# Mainboard_Encoder_Interface.net
KiCad netlist of a schematic drawn in Altium Designer
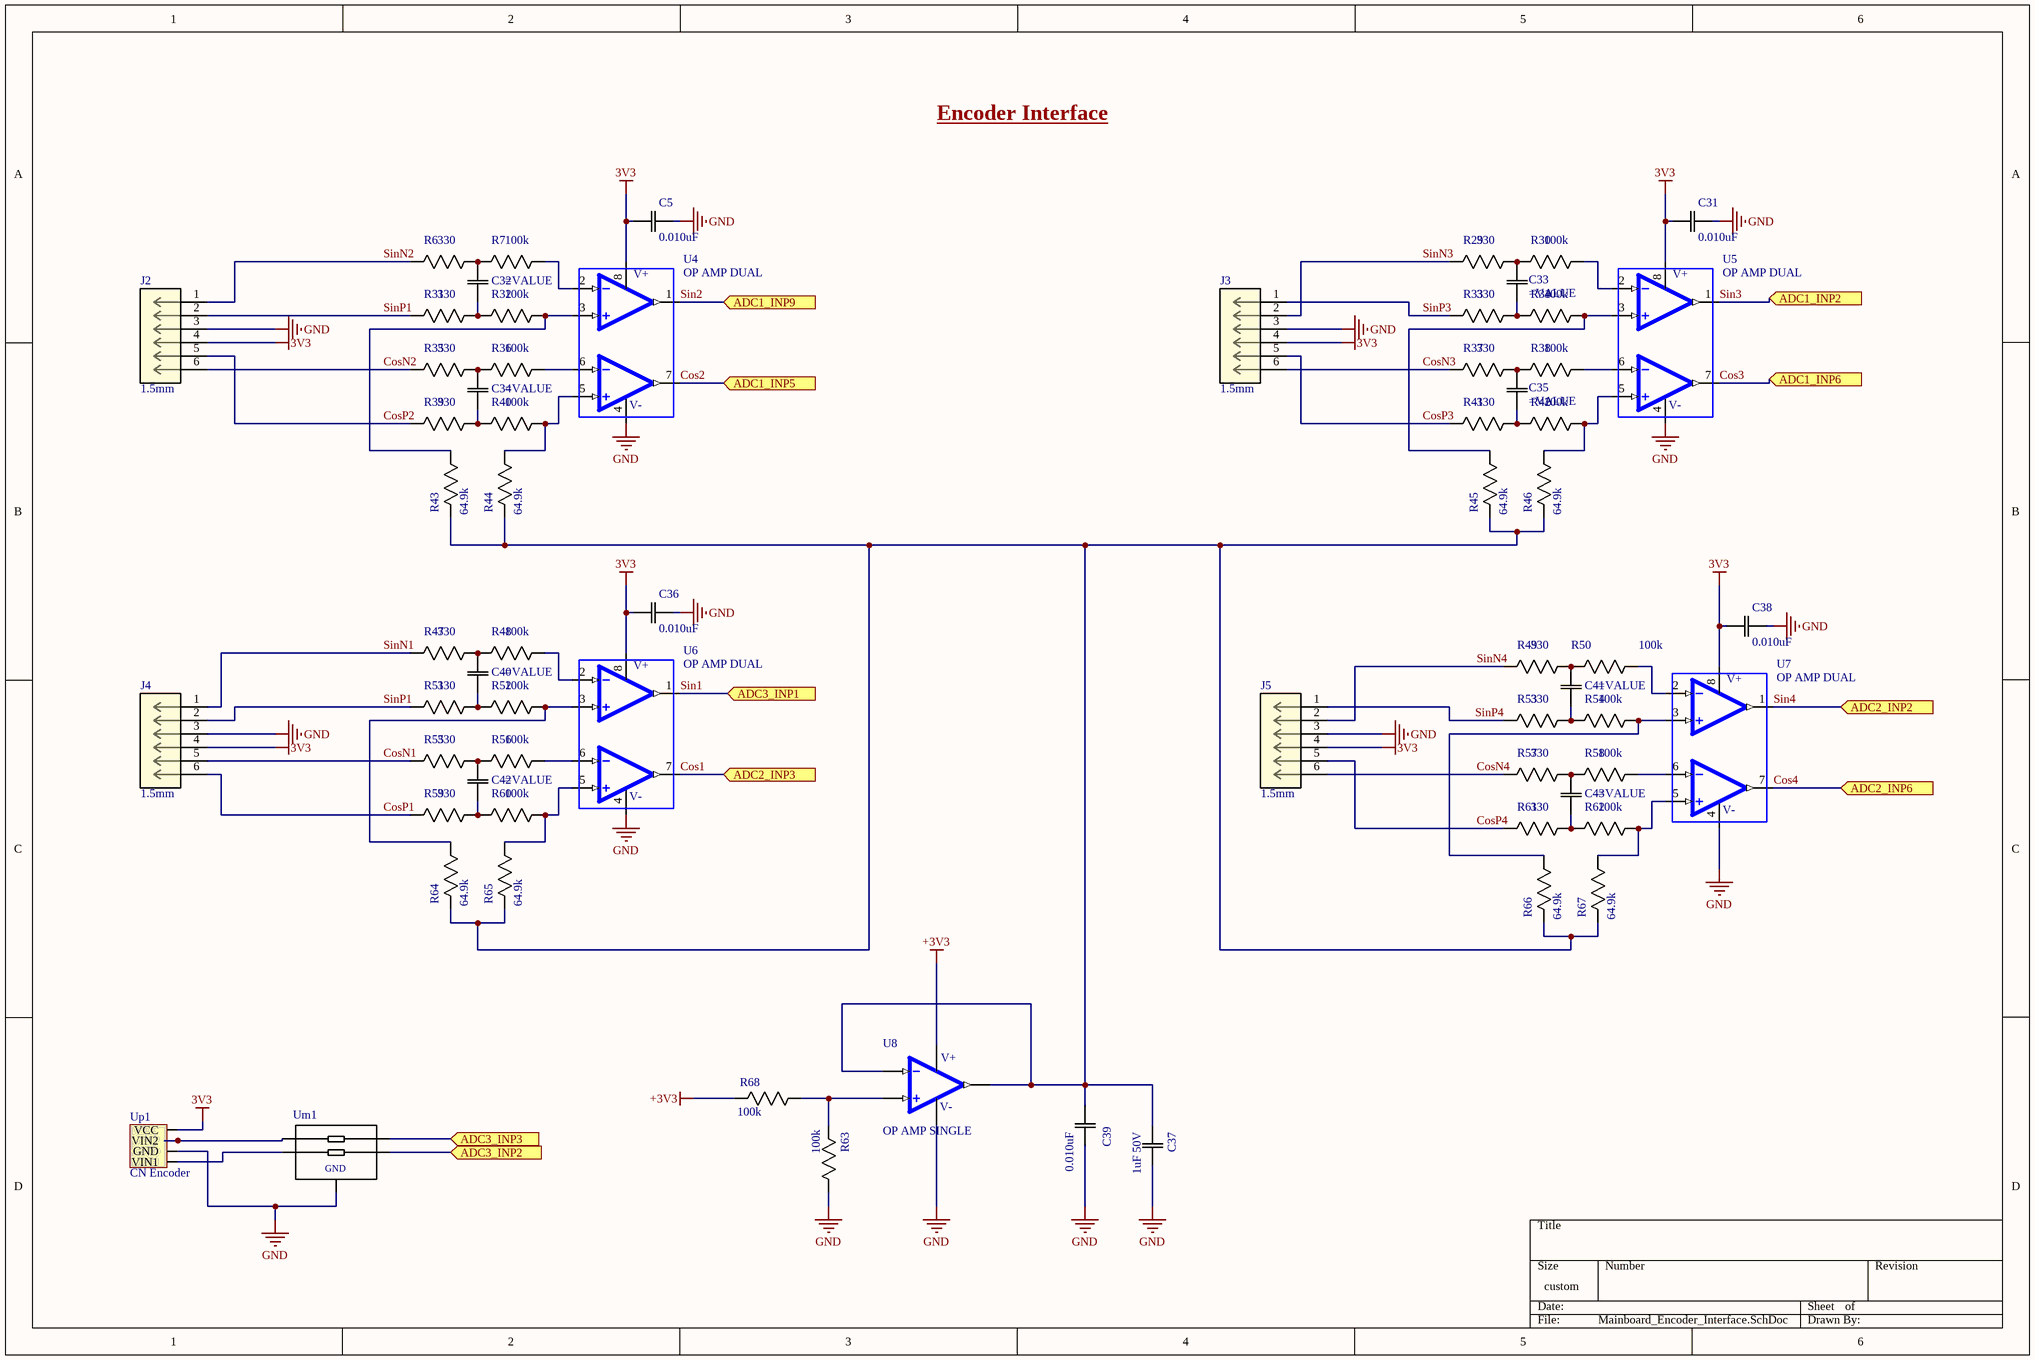
[diagram p0: Mainboard_Encoder_Interface.SchDoc]

(export (version "E")
  (design (tool "Eeschema 10.0.6"))
  (components
    (comp (ref "C5")
      (value "0.010uF")
      (footprint "0603")
      (description "CAP CER 0.010UF 50V X7R 0603/0805")
      (fields (field (name "TOLERANCE") "10%"))
      (libsource (lib "AltiumLibraries") (part "CAP 0.010uF 50V"))
    )
    (comp (ref "C31")
      (value "0.010uF")
      (footprint "0603")
      (description "CAP CER 0.010UF 50V X7R 0603/0805")
      (fields (field (name "TOLERANCE") "10%"))
      (libsource (lib "AltiumLibraries") (part "CAP 0.010uF 50V"))
    )
    (comp (ref "C32") (value "~") (libsource (lib "AltiumLibraries") (part "CAPACITOR_SCH")))
    (comp (ref "C33") (value "~") (libsource (lib "AltiumLibraries") (part "CAPACITOR_SCH")))
    (comp (ref "C34") (value "~") (libsource (lib "AltiumLibraries") (part "CAPACITOR_SCH")))
    (comp (ref "C35") (value "~") (libsource (lib "AltiumLibraries") (part "CAPACITOR_SCH")))
    (comp (ref "C36")
      (value "0.010uF")
      (footprint "0603")
      (description "CAP CER 0.010UF 50V X7R 0603/0805")
      (fields (field (name "TOLERANCE") "10%"))
      (libsource (lib "AltiumLibraries") (part "CAP 0.010uF 50V"))
    )
    (comp (ref "C37")
      (value "1uF 50V")
      (footprint "0805")
      (description "CAP CER 1UF 50V X7R 0805")
      (fields (field (name "TOLERANCE") "10%"))
      (libsource (lib "AltiumLibraries") (part "CAP 1uF 50V"))
    )
    (comp (ref "C38")
      (value "0.010uF")
      (footprint "0603")
      (description "CAP CER 0.010UF 50V X7R 0603/0805")
      (fields (field (name "TOLERANCE") "10%"))
      (libsource (lib "AltiumLibraries") (part "CAP 0.010uF 50V"))
    )
    (comp (ref "C39")
      (value "0.010uF")
      (footprint "0603")
      (description "CAP CER 0.010UF 50V X7R 0603/0805")
      (fields (field (name "TOLERANCE") "10%"))
      (libsource (lib "AltiumLibraries") (part "CAP 0.010uF 50V"))
    )
    (comp (ref "C40") (value "~") (libsource (lib "AltiumLibraries") (part "CAPACITOR_SCH")))
    (comp (ref "C41") (value "~") (libsource (lib "AltiumLibraries") (part "CAPACITOR_SCH")))
    (comp (ref "C42") (value "~") (libsource (lib "AltiumLibraries") (part "CAPACITOR_SCH")))
    (comp (ref "C43") (value "~") (libsource (lib "AltiumLibraries") (part "CAPACITOR_SCH")))
    (comp (ref "J2")
      (value "1.5mm")
      (footprint "6POS JST")
      (description "Conn Shrouded Header HDR 6 POS 1.5mm Solder RA Thru-Hole Box")
      (fields (field (name "MANUFACTURER") "JST") (field (name "MANUFACTURER PART NUMBER") "S6B-ZR(LF)(SN)"))
      (libsource (lib "AltiumLibraries") (part "CN 6POS JST RA"))
    )
    (comp (ref "J3")
      (value "1.5mm")
      (footprint "6POS JST")
      (description "Conn Shrouded Header HDR 6 POS 1.5mm Solder RA Thru-Hole Box")
      (fields (field (name "MANUFACTURER") "JST") (field (name "MANUFACTURER PART NUMBER") "S6B-ZR(LF)(SN)"))
      (libsource (lib "AltiumLibraries") (part "CN 6POS JST RA"))
    )
    (comp (ref "J4")
      (value "1.5mm")
      (footprint "6POS JST")
      (description "Conn Shrouded Header HDR 6 POS 1.5mm Solder RA Thru-Hole Box")
      (fields (field (name "MANUFACTURER") "JST") (field (name "MANUFACTURER PART NUMBER") "S6B-ZR(LF)(SN)"))
      (libsource (lib "AltiumLibraries") (part "CN 6POS JST RA"))
    )
    (comp (ref "J5")
      (value "1.5mm")
      (footprint "6POS JST")
      (description "Conn Shrouded Header HDR 6 POS 1.5mm Solder RA Thru-Hole Box")
      (fields (field (name "MANUFACTURER") "JST") (field (name "MANUFACTURER PART NUMBER") "S6B-ZR(LF)(SN)"))
      (libsource (lib "AltiumLibraries") (part "CN 6POS JST RA"))
    )
    (comp (ref "R6")
      (value "330")
      (footprint "0805")
      (description "RES SMD 330 OHM 1% 1/8W 0805")
      (fields (field (name "TOLERANCE") "1%"))
      (libsource (lib "") (part "RES 330.0 1/8W - 1%_1"))
    )
    (comp (ref "R7")
      (value "100k")
      (footprint "0805")
      (description "RES SMD 100K OHM 1% 1/8W 0805")
      (fields (field (name "TOLERANCE") "1%"))
      (libsource (lib "") (part "RES 100k 1/8W - 1%_1"))
    )
    (comp (ref "R29")
      (value "330")
      (footprint "0805")
      (description "RES SMD 330 OHM 1% 1/8W 0805")
      (fields (field (name "TOLERANCE") "1%"))
      (libsource (lib "") (part "RES 330.0 1/8W - 1%_1"))
    )
    (comp (ref "R30")
      (value "100k")
      (footprint "0805")
      (description "RES SMD 100K OHM 1% 1/8W 0805")
      (fields (field (name "TOLERANCE") "1%"))
      (libsource (lib "") (part "RES 100k 1/8W - 1%_1"))
    )
    (comp (ref "R31")
      (value "330")
      (footprint "0805")
      (description "RES SMD 330 OHM 1% 1/8W 0805")
      (fields (field (name "TOLERANCE") "1%"))
      (libsource (lib "AltiumLibraries") (part "RES 330.0 1/8W - 1%"))
    )
    (comp (ref "R32")
      (value "100k")
      (footprint "0805")
      (description "RES SMD 100K OHM 1% 1/8W 0805")
      (fields (field (name "TOLERANCE") "1%"))
      (libsource (lib "AltiumLibraries") (part "RES 100k 1/8W - 1%"))
    )
    (comp (ref "R33")
      (value "330")
      (footprint "0805")
      (description "RES SMD 330 OHM 1% 1/8W 0805")
      (fields (field (name "TOLERANCE") "1%"))
      (libsource (lib "AltiumLibraries") (part "RES 330.0 1/8W - 1%"))
    )
    (comp (ref "R34")
      (value "100k")
      (footprint "0805")
      (description "RES SMD 100K OHM 1% 1/8W 0805")
      (fields (field (name "TOLERANCE") "1%"))
      (libsource (lib "AltiumLibraries") (part "RES 100k 1/8W - 1%"))
    )
    (comp (ref "R35")
      (value "330")
      (footprint "0805")
      (description "RES SMD 330 OHM 1% 1/8W 0805")
      (fields (field (name "TOLERANCE") "1%"))
      (libsource (lib "") (part "RES 330.0 1/8W - 1%_1"))
    )
    (comp (ref "R36")
      (value "100k")
      (footprint "0805")
      (description "RES SMD 100K OHM 1% 1/8W 0805")
      (fields (field (name "TOLERANCE") "1%"))
      (libsource (lib "") (part "RES 100k 1/8W - 1%_1"))
    )
    (comp (ref "R37")
      (value "330")
      (footprint "0805")
      (description "RES SMD 330 OHM 1% 1/8W 0805")
      (fields (field (name "TOLERANCE") "1%"))
      (libsource (lib "") (part "RES 330.0 1/8W - 1%_1"))
    )
    (comp (ref "R38")
      (value "100k")
      (footprint "0805")
      (description "RES SMD 100K OHM 1% 1/8W 0805")
      (fields (field (name "TOLERANCE") "1%"))
      (libsource (lib "") (part "RES 100k 1/8W - 1%_1"))
    )
    (comp (ref "R39")
      (value "330")
      (footprint "0805")
      (description "RES SMD 330 OHM 1% 1/8W 0805")
      (fields (field (name "TOLERANCE") "1%"))
      (libsource (lib "AltiumLibraries") (part "RES 330.0 1/8W - 1%"))
    )
    (comp (ref "R40")
      (value "100k")
      (footprint "0805")
      (description "RES SMD 100K OHM 1% 1/8W 0805")
      (fields (field (name "TOLERANCE") "1%"))
      (libsource (lib "AltiumLibraries") (part "RES 100k 1/8W - 1%"))
    )
    (comp (ref "R41")
      (value "330")
      (footprint "0805")
      (description "RES SMD 330 OHM 1% 1/8W 0805")
      (fields (field (name "TOLERANCE") "1%"))
      (libsource (lib "AltiumLibraries") (part "RES 330.0 1/8W - 1%"))
    )
    (comp (ref "R42")
      (value "100k")
      (footprint "0805")
      (description "RES SMD 100K OHM 1% 1/8W 0805")
      (fields (field (name "TOLERANCE") "1%"))
      (libsource (lib "AltiumLibraries") (part "RES 100k 1/8W - 1%"))
    )
    (comp (ref "R43")
      (value "64.9k")
      (footprint "0805")
      (description "RES SMD 64.9K OHM 1% 1/8W 0805")
      (fields (field (name "TOLERANCE") "1%"))
      (libsource (lib "AltiumLibraries") (part "RES 64.9k 1/8W"))
    )
    (comp (ref "R44")
      (value "64.9k")
      (footprint "0805")
      (description "RES SMD 64.9K OHM 1% 1/8W 0805")
      (fields (field (name "TOLERANCE") "1%"))
      (libsource (lib "AltiumLibraries") (part "RES 64.9k 1/8W"))
    )
    (comp (ref "R45")
      (value "64.9k")
      (footprint "0805")
      (description "RES SMD 64.9K OHM 1% 1/8W 0805")
      (fields (field (name "TOLERANCE") "1%"))
      (libsource (lib "AltiumLibraries") (part "RES 64.9k 1/8W"))
    )
    (comp (ref "R46")
      (value "64.9k")
      (footprint "0805")
      (description "RES SMD 64.9K OHM 1% 1/8W 0805")
      (fields (field (name "TOLERANCE") "1%"))
      (libsource (lib "AltiumLibraries") (part "RES 64.9k 1/8W"))
    )
    (comp (ref "R47")
      (value "330")
      (footprint "0805")
      (description "RES SMD 330 OHM 1% 1/8W 0805")
      (fields (field (name "TOLERANCE") "1%"))
      (libsource (lib "") (part "RES 330.0 1/8W - 1%_1"))
    )
    (comp (ref "R48")
      (value "100k")
      (footprint "0805")
      (description "RES SMD 100K OHM 1% 1/8W 0805")
      (fields (field (name "TOLERANCE") "1%"))
      (libsource (lib "") (part "RES 100k 1/8W - 1%_1"))
    )
    (comp (ref "R49")
      (value "330")
      (footprint "0805")
      (description "RES SMD 330 OHM 1% 1/8W 0805")
      (fields (field (name "TOLERANCE") "1%"))
      (libsource (lib "") (part "RES 330.0 1/8W - 1%_1"))
    )
    (comp (ref "R50")
      (value "100k")
      (footprint "0805")
      (description "RES SMD 100K OHM 1% 1/8W 0805")
      (fields (field (name "TOLERANCE") "1%"))
      (libsource (lib "") (part "RES 100k 1/8W - 1%_1"))
    )
    (comp (ref "R51")
      (value "330")
      (footprint "0805")
      (description "RES SMD 330 OHM 1% 1/8W 0805")
      (fields (field (name "TOLERANCE") "1%"))
      (libsource (lib "AltiumLibraries") (part "RES 330.0 1/8W - 1%"))
    )
    (comp (ref "R52")
      (value "100k")
      (footprint "0805")
      (description "RES SMD 100K OHM 1% 1/8W 0805")
      (fields (field (name "TOLERANCE") "1%"))
      (libsource (lib "AltiumLibraries") (part "RES 100k 1/8W - 1%"))
    )
    (comp (ref "R53")
      (value "330")
      (footprint "0805")
      (description "RES SMD 330 OHM 1% 1/8W 0805")
      (fields (field (name "TOLERANCE") "1%"))
      (libsource (lib "AltiumLibraries") (part "RES 330.0 1/8W - 1%"))
    )
    (comp (ref "R54")
      (value "100k")
      (footprint "0805")
      (description "RES SMD 100K OHM 1% 1/8W 0805")
      (fields (field (name "TOLERANCE") "1%"))
      (libsource (lib "AltiumLibraries") (part "RES 100k 1/8W - 1%"))
    )
    (comp (ref "R55")
      (value "330")
      (footprint "0805")
      (description "RES SMD 330 OHM 1% 1/8W 0805")
      (fields (field (name "TOLERANCE") "1%"))
      (libsource (lib "") (part "RES 330.0 1/8W - 1%_1"))
    )
    (comp (ref "R56")
      (value "100k")
      (footprint "0805")
      (description "RES SMD 100K OHM 1% 1/8W 0805")
      (fields (field (name "TOLERANCE") "1%"))
      (libsource (lib "") (part "RES 100k 1/8W - 1%_1"))
    )
    (comp (ref "R57")
      (value "330")
      (footprint "0805")
      (description "RES SMD 330 OHM 1% 1/8W 0805")
      (fields (field (name "TOLERANCE") "1%"))
      (libsource (lib "") (part "RES 330.0 1/8W - 1%_1"))
    )
    (comp (ref "R58")
      (value "100k")
      (footprint "0805")
      (description "RES SMD 100K OHM 1% 1/8W 0805")
      (fields (field (name "TOLERANCE") "1%"))
      (libsource (lib "") (part "RES 100k 1/8W - 1%_1"))
    )
    (comp (ref "R59")
      (value "330")
      (footprint "0805")
      (description "RES SMD 330 OHM 1% 1/8W 0805")
      (fields (field (name "TOLERANCE") "1%"))
      (libsource (lib "AltiumLibraries") (part "RES 330.0 1/8W - 1%"))
    )
    (comp (ref "R60")
      (value "100k")
      (footprint "0805")
      (description "RES SMD 100K OHM 1% 1/8W 0805")
      (fields (field (name "TOLERANCE") "1%"))
      (libsource (lib "AltiumLibraries") (part "RES 100k 1/8W - 1%"))
    )
    (comp (ref "R61")
      (value "330")
      (footprint "0805")
      (description "RES SMD 330 OHM 1% 1/8W 0805")
      (fields (field (name "TOLERANCE") "1%"))
      (libsource (lib "AltiumLibraries") (part "RES 330.0 1/8W - 1%"))
    )
    (comp (ref "R62")
      (value "100k")
      (footprint "0805")
      (description "RES SMD 100K OHM 1% 1/8W 0805")
      (fields (field (name "TOLERANCE") "1%"))
      (libsource (lib "AltiumLibraries") (part "RES 100k 1/8W - 1%"))
    )
    (comp (ref "R63")
      (value "100k")
      (footprint "0805")
      (description "RES SMD 100K OHM 1% 1/8W 0805")
      (fields (field (name "TOLERANCE") "1%"))
      (libsource (lib "AltiumLibraries") (part "RES 100k 1/8W - 1%"))
    )
    (comp (ref "R64")
      (value "64.9k")
      (footprint "0805")
      (description "RES SMD 64.9K OHM 1% 1/8W 0805")
      (fields (field (name "TOLERANCE") "1%"))
      (libsource (lib "AltiumLibraries") (part "RES 64.9k 1/8W"))
    )
    (comp (ref "R65")
      (value "64.9k")
      (footprint "0805")
      (description "RES SMD 64.9K OHM 1% 1/8W 0805")
      (fields (field (name "TOLERANCE") "1%"))
      (libsource (lib "AltiumLibraries") (part "RES 64.9k 1/8W"))
    )
    (comp (ref "R66")
      (value "64.9k")
      (footprint "0805")
      (description "RES SMD 64.9K OHM 1% 1/8W 0805")
      (fields (field (name "TOLERANCE") "1%"))
      (libsource (lib "AltiumLibraries") (part "RES 64.9k 1/8W"))
    )
    (comp (ref "R67")
      (value "64.9k")
      (footprint "0805")
      (description "RES SMD 64.9K OHM 1% 1/8W 0805")
      (fields (field (name "TOLERANCE") "1%"))
      (libsource (lib "AltiumLibraries") (part "RES 64.9k 1/8W"))
    )
    (comp (ref "R68")
      (value "100k")
      (footprint "0805")
      (description "RES SMD 100K OHM 1% 1/8W 0805")
      (fields (field (name "TOLERANCE") "1%"))
      (libsource (lib "AltiumLibraries") (part "RES 100k 1/8W - 1%"))
    )
    (comp (ref "U4")
      (value "OP AMP DUAL")
      (footprint "8-MSOP")
      (description "IC OPAMP VFB 50KHZ RRO 8MSOP")
      (fields
        (field (name "MANUFACTURER") "Analog Devices")
        (field (name "MANUFACTURER PART NUMBER") "ADA4505-2ARMZ")
      )
      (libsource (lib "AltiumLibraries") (part "OP AMP DUAL"))
    )
    (comp (ref "U5")
      (value "OP AMP DUAL")
      (footprint "8-MSOP")
      (description "IC OPAMP VFB 50KHZ RRO 8MSOP")
      (fields
        (field (name "MANUFACTURER") "Analog Devices")
        (field (name "MANUFACTURER PART NUMBER") "ADA4505-2ARMZ")
      )
      (libsource (lib "AltiumLibraries") (part "OP AMP DUAL"))
    )
    (comp (ref "U6")
      (value "OP AMP DUAL")
      (footprint "8-MSOP")
      (description "IC OPAMP VFB 50KHZ RRO 8MSOP")
      (fields
        (field (name "MANUFACTURER") "Analog Devices")
        (field (name "MANUFACTURER PART NUMBER") "ADA4505-2ARMZ")
      )
      (libsource (lib "AltiumLibraries") (part "OP AMP DUAL"))
    )
    (comp (ref "U7")
      (value "OP AMP DUAL")
      (footprint "8-MSOP")
      (description "IC OPAMP VFB 50KHZ RRO 8MSOP")
      (fields
        (field (name "MANUFACTURER") "Analog Devices")
        (field (name "MANUFACTURER PART NUMBER") "ADA4505-2ARMZ")
      )
      (libsource (lib "AltiumLibraries") (part "OP AMP DUAL"))
    )
    (comp (ref "U8")
      (value "OP AMP SINGLE")
      (footprint "SOT95P280X145-5N")
      (description "ANALOG DEVICES - ADA4505-1ARJZ-R7 - IC, AMPLIF. OPER., R-R, CMOS, SOT23-5")
      (fields
        (field (name "MANUFACTURER") "Analog Devices")
        (field (name "MANUFACTURER PART NUMBER") "ADA4505-1ARJZ-R7")
      )
      (libsource (lib "AltiumLibraries") (part "OP AMP SINGLE"))
    )
    (comp (ref "Um1")
      (value "EMI")
      (footprint "SOT-665")
      (description "FILTER RC(PI) 100 OHM/19PF SMD")
      (fields (field (name "MF") "Nexperia USA Inc.") (field (name "MP") "IP4256CZ5-W,115"))
      (libsource (lib "AltiumLibraries") (part "EMI FILTER IP4256CZ5-W"))
    )
    (comp (ref "Up1")
      (value "CN Encoder")
      (footprint "EncoderConnector")
      (description "CN HDR R/A 4POS 1.5MM")
      (fields (field (name "MF") "JST Sales America Inc.") (field (name "MP") "S4B-ZR(LF)(SN)"))
      (libsource (lib "AltiumLibraries") (part "CN HDR 4POS"))
    )
  )
  (nets
    (net (code "1") (name "+3V3") (class "Default")
      (node (ref "R68") (pin "2") (pinfunction "R2_2") (pintype "passive"))
      (node (ref "U8") (pin "5") (pinfunction "V+_5") (pintype "power_in"))
    )
    (net (code "2") (name "/ADC3_INP2") (class "Default")
      (node (ref "Um1") (pin "4") (pinfunction "P$4_4") (pintype "passive"))
    )
    (net (code "3") (name "/ADC3_INP3") (class "Default")
      (node (ref "Um1") (pin "5") (pinfunction "P$5_5") (pintype "passive"))
    )
    (net (code "4") (name "/Cos1") (class "Default")
      (node (ref "U6") (pin "7") (pinfunction "OUTB_7") (pintype "output"))
    )
    (net (code "5") (name "/Cos2") (class "Default")
      (node (ref "U4") (pin "7") (pinfunction "OUTB_7") (pintype "output"))
    )
    (net (code "6") (name "/Cos3") (class "Default")
      (node (ref "U5") (pin "7") (pinfunction "OUTB_7") (pintype "output"))
    )
    (net (code "7") (name "/Cos4") (class "Default")
      (node (ref "U7") (pin "7") (pinfunction "OUTB_7") (pintype "output"))
    )
    (net (code "8") (name "/CosN1") (class "Default")
      (node (ref "J4") (pin "5") (pinfunction "5_5") (pintype "passive"))
      (node (ref "R55") (pin "2") (pinfunction "R2_2") (pintype "passive"))
    )
    (net (code "9") (name "/CosN2") (class "Default")
      (node (ref "J2") (pin "6") (pinfunction "6_6") (pintype "passive"))
      (node (ref "R35") (pin "2") (pinfunction "R2_2") (pintype "passive"))
    )
    (net (code "10") (name "/CosN3") (class "Default")
      (node (ref "J3") (pin "6") (pinfunction "6_6") (pintype "passive"))
      (node (ref "R37") (pin "2") (pinfunction "R2_2") (pintype "passive"))
    )
    (net (code "11") (name "/CosN4") (class "Default")
      (node (ref "J5") (pin "6") (pinfunction "6_6") (pintype "passive"))
      (node (ref "R57") (pin "2") (pinfunction "R2_2") (pintype "passive"))
    )
    (net (code "12") (name "/CosP1") (class "Default")
      (node (ref "J4") (pin "6") (pinfunction "6_6") (pintype "passive"))
      (node (ref "R59") (pin "2") (pinfunction "R2_2") (pintype "passive"))
    )
    (net (code "13") (name "/CosP2") (class "Default")
      (node (ref "J2") (pin "5") (pinfunction "5_5") (pintype "passive"))
      (node (ref "R39") (pin "2") (pinfunction "R2_2") (pintype "passive"))
    )
    (net (code "14") (name "/CosP3") (class "Default")
      (node (ref "J3") (pin "5") (pinfunction "5_5") (pintype "passive"))
      (node (ref "R41") (pin "2") (pinfunction "R2_2") (pintype "passive"))
    )
    (net (code "15") (name "/CosP4") (class "Default")
      (node (ref "J5") (pin "5") (pinfunction "5_5") (pintype "passive"))
      (node (ref "R61") (pin "2") (pinfunction "R2_2") (pintype "passive"))
    )
    (net (code "16") (name "/Sin1") (class "Default")
      (node (ref "U6") (pin "1") (pinfunction "OUTA_1") (pintype "output"))
    )
    (net (code "17") (name "/Sin2") (class "Default")
      (node (ref "U4") (pin "1") (pinfunction "OUTA_1") (pintype "output"))
    )
    (net (code "18") (name "/Sin3") (class "Default")
      (node (ref "U5") (pin "1") (pinfunction "OUTA_1") (pintype "output"))
    )
    (net (code "19") (name "/Sin4") (class "Default")
      (node (ref "U7") (pin "1") (pinfunction "OUTA_1") (pintype "output"))
    )
    (net (code "20") (name "/SinN1") (class "Default")
      (node (ref "J4") (pin "1") (pinfunction "1_1") (pintype "passive"))
      (node (ref "R47") (pin "2") (pinfunction "R2_2") (pintype "passive"))
    )
    (net (code "21") (name "/SinN2") (class "Default")
      (node (ref "J2") (pin "1") (pinfunction "1_1") (pintype "passive"))
      (node (ref "R6") (pin "2") (pinfunction "R2_2") (pintype "passive"))
    )
    (net (code "22") (name "/SinN3") (class "Default")
      (node (ref "J3") (pin "2") (pinfunction "2_2") (pintype "passive"))
      (node (ref "R29") (pin "2") (pinfunction "R2_2") (pintype "passive"))
    )
    (net (code "23") (name "/SinN4") (class "Default")
      (node (ref "J5") (pin "2") (pinfunction "2_2") (pintype "passive"))
      (node (ref "R49") (pin "2") (pinfunction "R2_2") (pintype "passive"))
    )
    (net (code "24") (name "/SinP1") (class "Default")
      (node (ref "J2") (pin "2") (pinfunction "2_2") (pintype "passive"))
      (node (ref "J4") (pin "2") (pinfunction "2_2") (pintype "passive"))
      (node (ref "R31") (pin "2") (pinfunction "R2_2") (pintype "passive"))
      (node (ref "R51") (pin "2") (pinfunction "R2_2") (pintype "passive"))
    )
    (net (code "25") (name "/SinP3") (class "Default")
      (node (ref "J3") (pin "1") (pinfunction "1_1") (pintype "passive"))
      (node (ref "R33") (pin "2") (pinfunction "R2_2") (pintype "passive"))
    )
    (net (code "26") (name "/SinP4") (class "Default")
      (node (ref "J5") (pin "1") (pinfunction "1_1") (pintype "passive"))
      (node (ref "R53") (pin "2") (pinfunction "R2_2") (pintype "passive"))
    )
    (net (code "27") (name "3V3") (class "Default")
      (node (ref "C31") (pin "1") (pinfunction "C1_1") (pintype "passive"))
      (node (ref "C36") (pin "1") (pinfunction "C1_1") (pintype "passive"))
      (node (ref "C38") (pin "1") (pinfunction "C1_1") (pintype "passive"))
      (node (ref "C5") (pin "1") (pinfunction "C1_1") (pintype "passive"))
      (node (ref "J2") (pin "4") (pinfunction "4_4") (pintype "passive"))
      (node (ref "J3") (pin "4") (pinfunction "4_4") (pintype "passive"))
      (node (ref "J4") (pin "4") (pinfunction "4_4") (pintype "passive"))
      (node (ref "J5") (pin "4") (pinfunction "4_4") (pintype "passive"))
      (node (ref "U4") (pin "8") (pinfunction "V+_8") (pintype "power_in"))
      (node (ref "U5") (pin "8") (pinfunction "V+_8") (pintype "power_in"))
      (node (ref "U6") (pin "8") (pinfunction "V+_8") (pintype "power_in"))
      (node (ref "U7") (pin "8") (pinfunction "V+_8") (pintype "power_in"))
      (node (ref "Up1") (pin "VCC") (pinfunction "VCC_VCC") (pintype "power_in"))
    )
    (net (code "28") (name "GND") (class "Default")
      (node (ref "C31") (pin "2") (pinfunction "C2_2") (pintype "passive"))
      (node (ref "C36") (pin "2") (pinfunction "C2_2") (pintype "passive"))
      (node (ref "C37") (pin "2") (pinfunction "C2_2") (pintype "passive"))
      (node (ref "C38") (pin "2") (pinfunction "C2_2") (pintype "passive"))
      (node (ref "C39") (pin "2") (pinfunction "C2_2") (pintype "passive"))
      (node (ref "C5") (pin "2") (pinfunction "C2_2") (pintype "passive"))
      (node (ref "J2") (pin "3") (pinfunction "3_3") (pintype "passive"))
      (node (ref "J3") (pin "3") (pinfunction "3_3") (pintype "passive"))
      (node (ref "J4") (pin "3") (pinfunction "3_3") (pintype "passive"))
      (node (ref "J5") (pin "3") (pinfunction "3_3") (pintype "passive"))
      (node (ref "R63") (pin "1") (pinfunction "R1_1") (pintype "passive"))
      (node (ref "U4") (pin "4") (pinfunction "V-_4") (pintype "power_in"))
      (node (ref "U5") (pin "4") (pinfunction "V-_4") (pintype "power_in"))
      (node (ref "U6") (pin "4") (pinfunction "V-_4") (pintype "power_in"))
      (node (ref "U7") (pin "4") (pinfunction "V-_4") (pintype "power_in"))
      (node (ref "U8") (pin "2") (pinfunction "V-_2") (pintype "power_in"))
      (node (ref "Um1") (pin "2") (pinfunction "P$2_2") (pintype "passive"))
      (node (ref "Up1") (pin "GND") (pinfunction "GND_GND") (pintype "power_in"))
    )
    (net (code "29") (name "Net-(C32-C1)") (class "Default")
      (node (ref "C32") (pin "1") (pinfunction "C1_1") (pintype "passive"))
      (node (ref "R31") (pin "1") (pinfunction "R1_1") (pintype "passive"))
      (node (ref "R32") (pin "2") (pinfunction "R2_2") (pintype "passive"))
    )
    (net (code "30") (name "Net-(C32-C2)") (class "Default")
      (node (ref "C32") (pin "2") (pinfunction "C2_2") (pintype "passive"))
      (node (ref "R6") (pin "1") (pinfunction "R1_1") (pintype "passive"))
      (node (ref "R7") (pin "2") (pinfunction "R2_2") (pintype "passive"))
    )
    (net (code "31") (name "Net-(C33-C1)") (class "Default")
      (node (ref "C33") (pin "1") (pinfunction "C1_1") (pintype "passive"))
      (node (ref "R33") (pin "1") (pinfunction "R1_1") (pintype "passive"))
      (node (ref "R34") (pin "2") (pinfunction "R2_2") (pintype "passive"))
    )
    (net (code "32") (name "Net-(C33-C2)") (class "Default")
      (node (ref "C33") (pin "2") (pinfunction "C2_2") (pintype "passive"))
      (node (ref "R29") (pin "1") (pinfunction "R1_1") (pintype "passive"))
      (node (ref "R30") (pin "2") (pinfunction "R2_2") (pintype "passive"))
    )
    (net (code "33") (name "Net-(C34-C1)") (class "Default")
      (node (ref "C34") (pin "1") (pinfunction "C1_1") (pintype "passive"))
      (node (ref "R39") (pin "1") (pinfunction "R1_1") (pintype "passive"))
      (node (ref "R40") (pin "2") (pinfunction "R2_2") (pintype "passive"))
    )
    (net (code "34") (name "Net-(C34-C2)") (class "Default")
      (node (ref "C34") (pin "2") (pinfunction "C2_2") (pintype "passive"))
      (node (ref "R35") (pin "1") (pinfunction "R1_1") (pintype "passive"))
      (node (ref "R36") (pin "2") (pinfunction "R2_2") (pintype "passive"))
    )
    (net (code "35") (name "Net-(C35-C1)") (class "Default")
      (node (ref "C35") (pin "1") (pinfunction "C1_1") (pintype "passive"))
      (node (ref "R41") (pin "1") (pinfunction "R1_1") (pintype "passive"))
      (node (ref "R42") (pin "2") (pinfunction "R2_2") (pintype "passive"))
    )
    (net (code "36") (name "Net-(C35-C2)") (class "Default")
      (node (ref "C35") (pin "2") (pinfunction "C2_2") (pintype "passive"))
      (node (ref "R37") (pin "1") (pinfunction "R1_1") (pintype "passive"))
      (node (ref "R38") (pin "2") (pinfunction "R2_2") (pintype "passive"))
    )
    (net (code "37") (name "Net-(C37-C1)") (class "Default")
      (node (ref "C37") (pin "1") (pinfunction "C1_1") (pintype "passive"))
      (node (ref "C39") (pin "1") (pinfunction "C1_1") (pintype "passive"))
      (node (ref "R43") (pin "2") (pinfunction "R2_2") (pintype "passive"))
      (node (ref "R44") (pin "2") (pinfunction "R2_2") (pintype "passive"))
      (node (ref "R45") (pin "2") (pinfunction "R2_2") (pintype "passive"))
      (node (ref "R46") (pin "2") (pinfunction "R2_2") (pintype "passive"))
      (node (ref "R64") (pin "2") (pinfunction "R2_2") (pintype "passive"))
      (node (ref "R65") (pin "2") (pinfunction "R2_2") (pintype "passive"))
      (node (ref "R66") (pin "2") (pinfunction "R2_2") (pintype "passive"))
      (node (ref "R67") (pin "2") (pinfunction "R2_2") (pintype "passive"))
      (node (ref "U8") (pin "1") (pinfunction "OUT_1") (pintype "output"))
      (node (ref "U8") (pin "4") (pinfunction "IN-_4") (pintype "input"))
    )
    (net (code "38") (name "Net-(C40-C1)") (class "Default")
      (node (ref "C40") (pin "1") (pinfunction "C1_1") (pintype "passive"))
      (node (ref "R51") (pin "1") (pinfunction "R1_1") (pintype "passive"))
      (node (ref "R52") (pin "2") (pinfunction "R2_2") (pintype "passive"))
    )
    (net (code "39") (name "Net-(C40-C2)") (class "Default")
      (node (ref "C40") (pin "2") (pinfunction "C2_2") (pintype "passive"))
      (node (ref "R47") (pin "1") (pinfunction "R1_1") (pintype "passive"))
      (node (ref "R48") (pin "2") (pinfunction "R2_2") (pintype "passive"))
    )
    (net (code "40") (name "Net-(C41-C1)") (class "Default")
      (node (ref "C41") (pin "1") (pinfunction "C1_1") (pintype "passive"))
      (node (ref "R53") (pin "1") (pinfunction "R1_1") (pintype "passive"))
      (node (ref "R54") (pin "2") (pinfunction "R2_2") (pintype "passive"))
    )
    (net (code "41") (name "Net-(C41-C2)") (class "Default")
      (node (ref "C41") (pin "2") (pinfunction "C2_2") (pintype "passive"))
      (node (ref "R49") (pin "1") (pinfunction "R1_1") (pintype "passive"))
      (node (ref "R50") (pin "2") (pinfunction "R2_2") (pintype "passive"))
    )
    (net (code "42") (name "Net-(C42-C1)") (class "Default")
      (node (ref "C42") (pin "1") (pinfunction "C1_1") (pintype "passive"))
      (node (ref "R59") (pin "1") (pinfunction "R1_1") (pintype "passive"))
      (node (ref "R60") (pin "2") (pinfunction "R2_2") (pintype "passive"))
    )
    (net (code "43") (name "Net-(C42-C2)") (class "Default")
      (node (ref "C42") (pin "2") (pinfunction "C2_2") (pintype "passive"))
      (node (ref "R55") (pin "1") (pinfunction "R1_1") (pintype "passive"))
      (node (ref "R56") (pin "2") (pinfunction "R2_2") (pintype "passive"))
    )
    (net (code "44") (name "Net-(C43-C1)") (class "Default")
      (node (ref "C43") (pin "1") (pinfunction "C1_1") (pintype "passive"))
      (node (ref "R61") (pin "1") (pinfunction "R1_1") (pintype "passive"))
      (node (ref "R62") (pin "2") (pinfunction "R2_2") (pintype "passive"))
    )
    (net (code "45") (name "Net-(C43-C2)") (class "Default")
      (node (ref "C43") (pin "2") (pinfunction "C2_2") (pintype "passive"))
      (node (ref "R57") (pin "1") (pinfunction "R1_1") (pintype "passive"))
      (node (ref "R58") (pin "2") (pinfunction "R2_2") (pintype "passive"))
    )
    (net (code "46") (name "Net-(R7-R1)") (class "Default")
      (node (ref "R7") (pin "1") (pinfunction "R1_1") (pintype "passive"))
      (node (ref "U4") (pin "2") (pinfunction "INA-_2") (pintype "input"))
    )
    (net (code "47") (name "Net-(R30-R1)") (class "Default")
      (node (ref "R30") (pin "1") (pinfunction "R1_1") (pintype "passive"))
      (node (ref "U5") (pin "2") (pinfunction "INA-_2") (pintype "input"))
    )
    (net (code "48") (name "Net-(R32-R1)") (class "Default")
      (node (ref "R32") (pin "1") (pinfunction "R1_1") (pintype "passive"))
      (node (ref "R43") (pin "1") (pinfunction "R1_1") (pintype "passive"))
      (node (ref "U4") (pin "3") (pinfunction "INA+_3") (pintype "input"))
    )
    (net (code "49") (name "Net-(R34-R1)") (class "Default")
      (node (ref "R34") (pin "1") (pinfunction "R1_1") (pintype "passive"))
      (node (ref "R45") (pin "1") (pinfunction "R1_1") (pintype "passive"))
      (node (ref "U5") (pin "3") (pinfunction "INA+_3") (pintype "input"))
    )
    (net (code "50") (name "Net-(R36-R1)") (class "Default")
      (node (ref "R36") (pin "1") (pinfunction "R1_1") (pintype "passive"))
      (node (ref "U4") (pin "6") (pinfunction "INB-_6") (pintype "input"))
    )
    (net (code "51") (name "Net-(R38-R1)") (class "Default")
      (node (ref "R38") (pin "1") (pinfunction "R1_1") (pintype "passive"))
      (node (ref "U5") (pin "6") (pinfunction "INB-_6") (pintype "input"))
    )
    (net (code "52") (name "Net-(R40-R1)") (class "Default")
      (node (ref "R40") (pin "1") (pinfunction "R1_1") (pintype "passive"))
      (node (ref "R44") (pin "1") (pinfunction "R1_1") (pintype "passive"))
      (node (ref "U4") (pin "5") (pinfunction "INB+_5") (pintype "input"))
    )
    (net (code "53") (name "Net-(R42-R1)") (class "Default")
      (node (ref "R42") (pin "1") (pinfunction "R1_1") (pintype "passive"))
      (node (ref "R46") (pin "1") (pinfunction "R1_1") (pintype "passive"))
      (node (ref "U5") (pin "5") (pinfunction "INB+_5") (pintype "input"))
    )
    (net (code "54") (name "Net-(R48-R1)") (class "Default")
      (node (ref "R48") (pin "1") (pinfunction "R1_1") (pintype "passive"))
      (node (ref "U6") (pin "2") (pinfunction "INA-_2") (pintype "input"))
    )
    (net (code "55") (name "Net-(R50-R1)") (class "Default")
      (node (ref "R50") (pin "1") (pinfunction "R1_1") (pintype "passive"))
      (node (ref "U7") (pin "2") (pinfunction "INA-_2") (pintype "input"))
    )
    (net (code "56") (name "Net-(R52-R1)") (class "Default")
      (node (ref "R52") (pin "1") (pinfunction "R1_1") (pintype "passive"))
      (node (ref "R64") (pin "1") (pinfunction "R1_1") (pintype "passive"))
      (node (ref "U6") (pin "3") (pinfunction "INA+_3") (pintype "input"))
    )
    (net (code "57") (name "Net-(R54-R1)") (class "Default")
      (node (ref "R54") (pin "1") (pinfunction "R1_1") (pintype "passive"))
      (node (ref "R66") (pin "1") (pinfunction "R1_1") (pintype "passive"))
      (node (ref "U7") (pin "3") (pinfunction "INA+_3") (pintype "input"))
    )
    (net (code "58") (name "Net-(R56-R1)") (class "Default")
      (node (ref "R56") (pin "1") (pinfunction "R1_1") (pintype "passive"))
      (node (ref "U6") (pin "6") (pinfunction "INB-_6") (pintype "input"))
    )
    (net (code "59") (name "Net-(R58-R1)") (class "Default")
      (node (ref "R58") (pin "1") (pinfunction "R1_1") (pintype "passive"))
      (node (ref "U7") (pin "6") (pinfunction "INB-_6") (pintype "input"))
    )
    (net (code "60") (name "Net-(R60-R1)") (class "Default")
      (node (ref "R60") (pin "1") (pinfunction "R1_1") (pintype "passive"))
      (node (ref "R65") (pin "1") (pinfunction "R1_1") (pintype "passive"))
      (node (ref "U6") (pin "5") (pinfunction "INB+_5") (pintype "input"))
    )
    (net (code "61") (name "Net-(R62-R1)") (class "Default")
      (node (ref "R62") (pin "1") (pinfunction "R1_1") (pintype "passive"))
      (node (ref "R67") (pin "1") (pinfunction "R1_1") (pintype "passive"))
      (node (ref "U7") (pin "5") (pinfunction "INB+_5") (pintype "input"))
    )
    (net (code "62") (name "Net-(R63-R2)") (class "Default")
      (node (ref "R63") (pin "2") (pinfunction "R2_2") (pintype "passive"))
      (node (ref "R68") (pin "1") (pinfunction "R1_1") (pintype "passive"))
      (node (ref "U8") (pin "3") (pinfunction "IN+_3") (pintype "input"))
    )
    (net (code "63") (name "Net-(Um1-P$1)") (class "Default")
      (node (ref "Um1") (pin "1") (pinfunction "P$1_1") (pintype "passive"))
      (node (ref "Up1") (pin "VIN2") (pinfunction "VIN2_VIN2") (pintype "input"))
    )
    (net (code "64") (name "Net-(Um1-P$3)") (class "Default")
      (node (ref "Um1") (pin "3") (pinfunction "P$3_3") (pintype "passive"))
      (node (ref "Up1") (pin "VIN1") (pinfunction "VIN1_VIN1") (pintype "input"))
    )
  )
)
